# Medicop_Schematic.net
KiCad netlist of a schematic drawn in Altium Designer
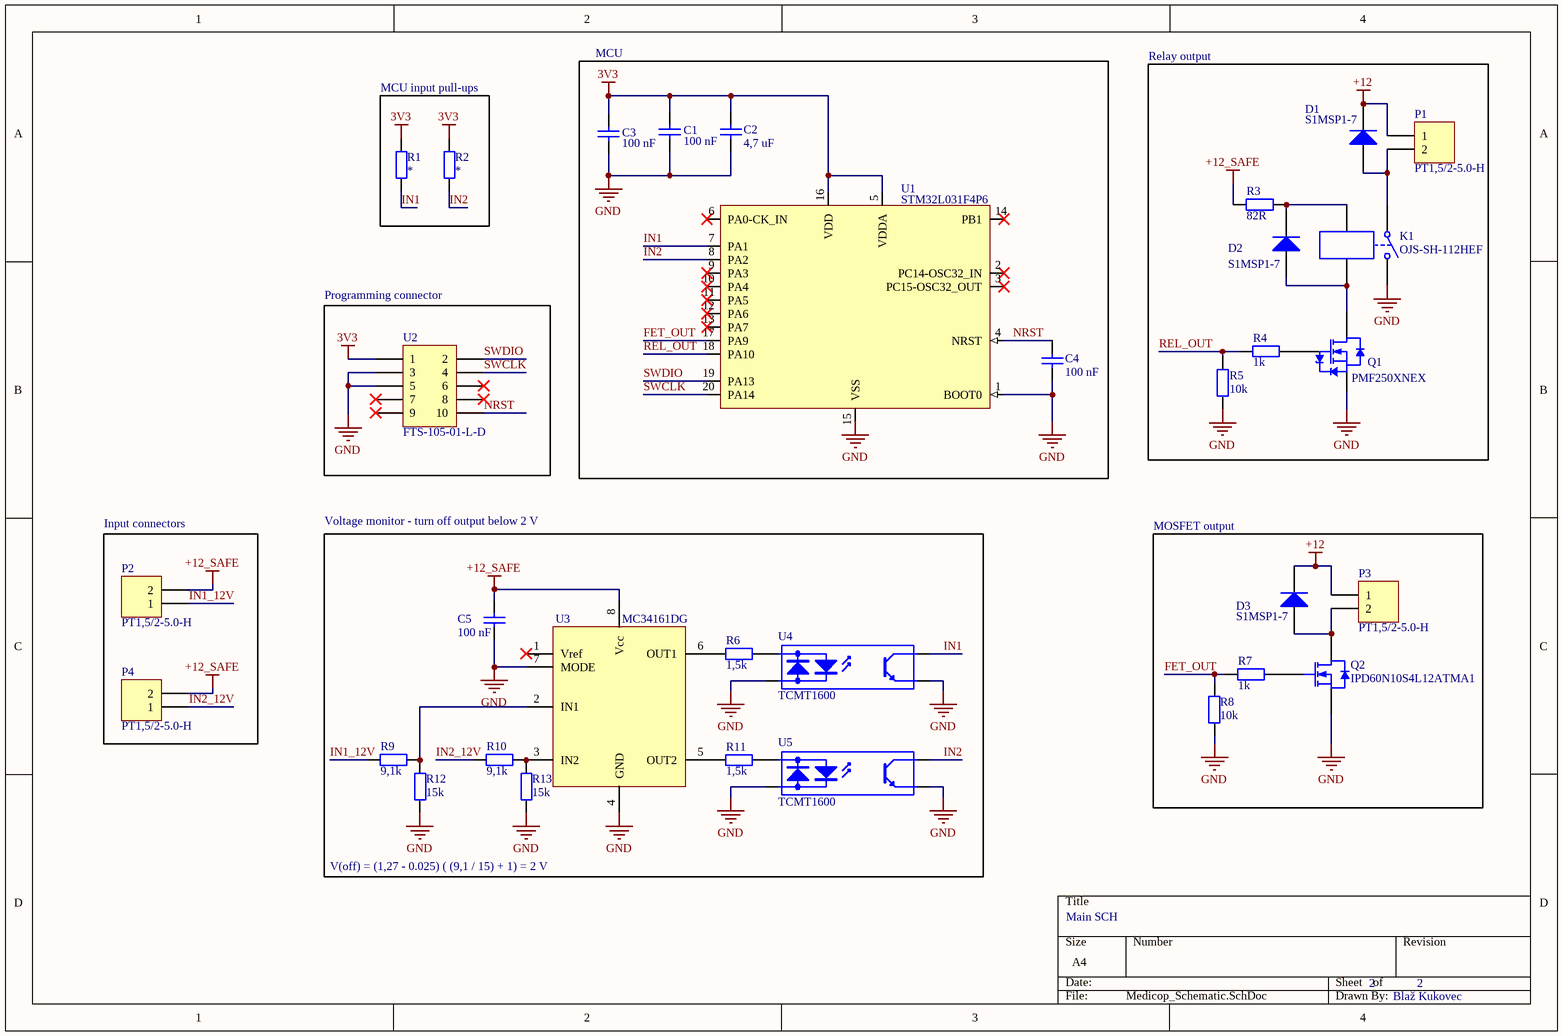
[diagram p0: Medicop_Schematic.SchDoc]

(export (version "E")
  (design (tool "Eeschema 10.0.6"))
  (components
    (comp (ref "C1")
      (value "100 nF")
      (footprint "C0603[1608]")
      (description "Capacitor")
      (fields (field (name "Comment") "Cap"))
      (libsource (lib "BK_Library") (part "Cap"))
    )
    (comp (ref "C2")
      (value "4,7 uF")
      (footprint "C0603[1608]")
      (description "Capacitor")
      (fields (field (name "Comment") "Cap"))
      (libsource (lib "BK_Library") (part "Cap"))
    )
    (comp (ref "C3")
      (value "100 nF")
      (footprint "C0603[1608]")
      (description "Capacitor")
      (fields (field (name "Comment") "Cap"))
      (libsource (lib "BK_Library") (part "Cap"))
    )
    (comp (ref "C4")
      (value "100 nF")
      (footprint "C0603[1608]")
      (description "Capacitor")
      (fields (field (name "Comment") "Cap"))
      (libsource (lib "BK_Library") (part "Cap"))
    )
    (comp (ref "C5")
      (value "100 nF")
      (footprint "C0603[1608]")
      (description "Capacitor")
      (fields (field (name "Comment") "Cap"))
      (libsource (lib "BK_Library") (part "Cap"))
    )
    (comp (ref "D1")
      (value "S1MSP1-7")
      (footprint "PowerDI123")
      (description "S1MSP1-7 -  Standard Power Diode")
      (libsource (lib "BK_Library") (part "S1MSP1-7"))
    )
    (comp (ref "D2")
      (value "S1MSP1-7")
      (footprint "PowerDI123")
      (description "S1MSP1-7 -  Standard Power Diode")
      (libsource (lib "BK_Library") (part "S1MSP1-7"))
    )
    (comp (ref "D3")
      (value "S1MSP1-7")
      (footprint "PowerDI123")
      (description "S1MSP1-7 -  Standard Power Diode")
      (libsource (lib "BK_Library") (part "S1MSP1-7"))
    )
    (comp (ref "K1")
      (value "OJS-SH-112HEF")
      (description "Power Relay, SPST-NO, 12 VDC, 16 A, OJS, Through Hole, Non Latching")
      (libsource (lib "BK_Library") (part "OJS-SH-112HEF"))
    )
    (comp (ref "P1")
      (value "PT1,5/2-5.0-H")
      (footprint "PT1,5/2-5.0-H")
      (description "Wire-To-Board Terminal Block, 5 mm, 2 Ways, 1.5 mm²")
      (libsource (lib "") (part "PT1,5/2-5.0-H_1"))
    )
    (comp (ref "P2")
      (value "PT1,5/2-5.0-H")
      (footprint "PT1,5/2-5.0-H")
      (description "Wire-To-Board Terminal Block, 5 mm, 2 Ways, 1.5 mm²")
      (libsource (lib "BK_Library") (part "PT1,5/2-5.0-H"))
    )
    (comp (ref "P3")
      (value "PT1,5/2-5.0-H")
      (footprint "PT1,5/2-5.0-H")
      (description "Wire-To-Board Terminal Block, 5 mm, 2 Ways, 1.5 mm²")
      (libsource (lib "") (part "PT1,5/2-5.0-H_1"))
    )
    (comp (ref "P4")
      (value "PT1,5/2-5.0-H")
      (footprint "PT1,5/2-5.0-H")
      (description "Wire-To-Board Terminal Block, 5 mm, 2 Ways, 1.5 mm²")
      (libsource (lib "BK_Library") (part "PT1,5/2-5.0-H"))
    )
    (comp (ref "Q1")
      (value "PMF250XNEX")
      (footprint "SC-70 (SOT323)")
      (description "Power MOSFET, N Channel, 30 V, 900 mA, 0.212 ohm")
      (libsource (lib "BK_Library") (part "PMF250XNEX"))
    )
    (comp (ref "Q2")
      (value "IPD60N10S4L12ATMA1")
      (footprint "DPAK (TO-252)")
      (description "Power MOSFET, N Channel, 100 V, 60 A, 0.0098 ohm, TO-252 (DPAK), Surface Mount")
      (libsource (lib "BK_Library") (part "IPD60N10S4L12ATMA1"))
    )
    (comp (ref "R1")
      (value "Res")
      (footprint "R0603[1608]")
      (description "Resistor")
      (fields (field (name "ALTIUM_VALUE") "*"))
      (libsource (lib "") (part "Res_1"))
    )
    (comp (ref "R2")
      (value "Res")
      (footprint "R0603[1608]")
      (description "Resistor")
      (fields (field (name "ALTIUM_VALUE") "*"))
      (libsource (lib "") (part "Res_1"))
    )
    (comp (ref "R3")
      (value "82R")
      (footprint "R1206[3216]")
      (description "Resistor")
      (fields (field (name "Comment") "Res"))
      (libsource (lib "") (part "Res_3"))
    )
    (comp (ref "R4")
      (value "1k")
      (footprint "R0603[1608]")
      (description "Resistor")
      (fields (field (name "Comment") "Res"))
      (libsource (lib "") (part "Res_3"))
    )
    (comp (ref "R5")
      (value "10k")
      (footprint "R0603[1608]")
      (description "Resistor")
      (fields (field (name "Comment") "Res"))
      (libsource (lib "") (part "Res_1"))
    )
    (comp (ref "R6")
      (value "1,5k")
      (footprint "R1206[3216]")
      (description "Resistor")
      (fields (field (name "Comment") "Res"))
      (libsource (lib "BK_Library") (part "Res"))
    )
    (comp (ref "R7")
      (value "1k")
      (footprint "R0603[1608]")
      (description "Resistor")
      (fields (field (name "Comment") "Res"))
      (libsource (lib "BK_Library") (part "Res"))
    )
    (comp (ref "R8")
      (value "10k")
      (footprint "R0603[1608]")
      (description "Resistor")
      (fields (field (name "Comment") "Res"))
      (libsource (lib "") (part "Res_2"))
    )
    (comp (ref "R9")
      (value "9,1k")
      (footprint "R0603[1608]")
      (description "Resistor")
      (fields (field (name "Comment") "Res"))
      (libsource (lib "") (part "Res_3"))
    )
    (comp (ref "R10")
      (value "9,1k")
      (footprint "R0603[1608]")
      (description "Resistor")
      (fields (field (name "Comment") "Res"))
      (libsource (lib "") (part "Res_3"))
    )
    (comp (ref "R11")
      (value "1,5k")
      (footprint "R1206[3216]")
      (description "Resistor")
      (fields (field (name "Comment") "Res"))
      (libsource (lib "BK_Library") (part "Res"))
    )
    (comp (ref "R12")
      (value "15k")
      (footprint "R0603[1608]")
      (description "Resistor")
      (fields (field (name "Comment") "Res"))
      (libsource (lib "") (part "Res_1"))
    )
    (comp (ref "R13")
      (value "15k")
      (footprint "R0603[1608]")
      (description "Resistor")
      (fields (field (name "Comment") "Res"))
      (libsource (lib "") (part "Res_1"))
    )
    (comp (ref "U1")
      (value "STM32L031F4P6")
      (footprint "TSSOP-20")
      (libsource (lib "BK_Library") (part "STM32L031F4P6"))
    )
    (comp (ref "U2")
      (value "FTS-105-01-L-D")
      (footprint "CON10_2x5_TU_FTS_SAI")
      (description "Pin Header, Wire-to-Board, 1.27 mm, 2 Rows, 10 Contacts, Through Hole, FTS")
      (libsource (lib "BK_Library") (part "FTS-105-01-L-D"))
    )
    (comp (ref "U3")
      (value "MC34161DG")
      (footprint "SOIC-8")
      (description "Voltage Monitor, 2 Monitors, 2 V to 40 V Supply, 1.27 V Threshold, Active-Low, MSOP-8")
      (libsource (lib "BK_Library") (part "MC34161DG"))
    )
    (comp (ref "U4") (value "TCMT1600") (footprint "SOP-4") (libsource (lib "BK_Library") (part "TCMT1600")))
    (comp (ref "U5") (value "TCMT1600") (footprint "SOP-4") (libsource (lib "BK_Library") (part "TCMT1600")))
  )
  (nets
    (net (code "1") (name "+12") (class "Default")
      (node (ref "D1") (pin "2") (pinfunction "K_2") (pintype "passive"))
      (node (ref "D3") (pin "2") (pinfunction "K_2") (pintype "passive"))
      (node (ref "P1") (pin "1") (pinfunction "1_1") (pintype "passive"))
      (node (ref "P3") (pin "1") (pinfunction "1_1") (pintype "passive"))
    )
    (net (code "2") (name "+12_SAFE") (class "Default")
      (node (ref "C5") (pin "2") (pinfunction "2_2") (pintype "passive"))
      (node (ref "P2") (pin "2") (pinfunction "2_2") (pintype "passive"))
      (node (ref "P4") (pin "2") (pinfunction "2_2") (pintype "passive"))
      (node (ref "R3") (pin "2") (pinfunction "2_2") (pintype "passive"))
      (node (ref "U3") (pin "8") (pinfunction "Vcc_8") (pintype "passive"))
    )
    (net (code "3") (name "/FET_OUT") (class "Default")
      (node (ref "R7") (pin "1") (pinfunction "1_1") (pintype "passive"))
      (node (ref "R8") (pin "1") (pinfunction "1_1") (pintype "passive"))
      (node (ref "U1") (pin "17") (pinfunction "PA9_17") (pintype "passive"))
    )
    (net (code "4") (name "/IN1") (class "Default")
      (node (ref "R1") (pin "1") (pinfunction "1_1") (pintype "passive"))
      (node (ref "U1") (pin "7") (pinfunction "PA1_7") (pintype "passive"))
      (node (ref "U4") (pin "4") (pinfunction "C_4") (pintype "passive"))
    )
    (net (code "5") (name "/IN1_12V") (class "Default")
      (node (ref "P2") (pin "1") (pinfunction "1_1") (pintype "passive"))
      (node (ref "R9") (pin "2") (pinfunction "2_2") (pintype "passive"))
    )
    (net (code "6") (name "/IN2") (class "Default")
      (node (ref "R2") (pin "1") (pinfunction "1_1") (pintype "passive"))
      (node (ref "U1") (pin "8") (pinfunction "PA2_8") (pintype "passive"))
      (node (ref "U5") (pin "4") (pinfunction "C_4") (pintype "passive"))
    )
    (net (code "7") (name "/IN2_12V") (class "Default")
      (node (ref "P4") (pin "1") (pinfunction "1_1") (pintype "passive"))
      (node (ref "R10") (pin "2") (pinfunction "2_2") (pintype "passive"))
    )
    (net (code "8") (name "/NRST") (class "Default")
      (node (ref "C4") (pin "2") (pinfunction "2_2") (pintype "passive"))
      (node (ref "U1") (pin "4") (pinfunction "NRST_4") (pintype "input"))
      (node (ref "U2") (pin "10") (pinfunction "10_10") (pintype "passive"))
    )
    (net (code "9") (name "/REL_OUT") (class "Default")
      (node (ref "R4") (pin "2") (pinfunction "2_2") (pintype "passive"))
      (node (ref "R5") (pin "2") (pinfunction "2_2") (pintype "passive"))
      (node (ref "U1") (pin "18") (pinfunction "PA10_18") (pintype "passive"))
    )
    (net (code "10") (name "/SWCLK") (class "Default")
      (node (ref "U1") (pin "20") (pinfunction "PA14_20") (pintype "passive"))
      (node (ref "U2") (pin "4") (pinfunction "4_4") (pintype "passive"))
    )
    (net (code "11") (name "/SWDIO") (class "Default")
      (node (ref "U1") (pin "19") (pinfunction "PA13_19") (pintype "passive"))
      (node (ref "U2") (pin "2") (pinfunction "2_2") (pintype "passive"))
    )
    (net (code "12") (name "3V3") (class "Default")
      (node (ref "C1") (pin "2") (pinfunction "2_2") (pintype "passive"))
      (node (ref "C2") (pin "2") (pinfunction "2_2") (pintype "passive"))
      (node (ref "C3") (pin "2") (pinfunction "2_2") (pintype "passive"))
      (node (ref "R1") (pin "2") (pinfunction "2_2") (pintype "passive"))
      (node (ref "R2") (pin "2") (pinfunction "2_2") (pintype "passive"))
      (node (ref "U1") (pin "16") (pinfunction "VDD_16") (pintype "power_in"))
      (node (ref "U1") (pin "5") (pinfunction "VDDA_5") (pintype "power_in"))
      (node (ref "U2") (pin "1") (pinfunction "1_1") (pintype "passive"))
    )
    (net (code "13") (name "GND") (class "Default")
      (node (ref "C1") (pin "1") (pinfunction "1_1") (pintype "passive"))
      (node (ref "C2") (pin "1") (pinfunction "1_1") (pintype "passive"))
      (node (ref "C3") (pin "1") (pinfunction "1_1") (pintype "passive"))
      (node (ref "C4") (pin "1") (pinfunction "1_1") (pintype "passive"))
      (node (ref "C5") (pin "1") (pinfunction "1_1") (pintype "passive"))
      (node (ref "K1") (pin "2") (pinfunction "2_2") (pintype "passive"))
      (node (ref "Q1") (pin "2") (pinfunction "S_2") (pintype "passive"))
      (node (ref "Q2") (pin "3") (pinfunction "S_3") (pintype "passive"))
      (node (ref "R12") (pin "1") (pinfunction "1_1") (pintype "passive"))
      (node (ref "R13") (pin "1") (pinfunction "1_1") (pintype "passive"))
      (node (ref "R5") (pin "1") (pinfunction "1_1") (pintype "passive"))
      (node (ref "R8") (pin "2") (pinfunction "2_2") (pintype "passive"))
      (node (ref "U1") (pin "1") (pinfunction "BOOT0_1") (pintype "input"))
      (node (ref "U1") (pin "15") (pinfunction "VSS_15") (pintype "power_in"))
      (node (ref "U2") (pin "3") (pinfunction "3_3") (pintype "passive"))
      (node (ref "U2") (pin "5") (pinfunction "5_5") (pintype "passive"))
      (node (ref "U3") (pin "4") (pinfunction "GND_4") (pintype "passive"))
      (node (ref "U3") (pin "7") (pinfunction "MODE_7") (pintype "passive"))
      (node (ref "U4") (pin "2") (pinfunction "K_2") (pintype "passive"))
      (node (ref "U4") (pin "3") (pinfunction "E_3") (pintype "passive"))
      (node (ref "U5") (pin "2") (pinfunction "K_2") (pintype "passive"))
      (node (ref "U5") (pin "3") (pinfunction "E_3") (pintype "passive"))
    )
    (net (code "14") (name "Net-(D1-A)") (class "Default")
      (node (ref "D1") (pin "1") (pinfunction "A_1") (pintype "passive"))
      (node (ref "K1") (pin "1") (pinfunction "1_1") (pintype "passive"))
      (node (ref "P1") (pin "2") (pinfunction "2_2") (pintype "passive"))
    )
    (net (code "15") (name "Net-(D2-A)") (class "Default")
      (node (ref "D2") (pin "1") (pinfunction "A_1") (pintype "passive"))
      (node (ref "K1") (pin "4") (pinfunction "4_4") (pintype "passive"))
      (node (ref "Q1") (pin "3") (pinfunction "D_3") (pintype "passive"))
    )
    (net (code "16") (name "Net-(D2-K)") (class "Default")
      (node (ref "D2") (pin "2") (pinfunction "K_2") (pintype "passive"))
      (node (ref "K1") (pin "3") (pinfunction "3_3") (pintype "passive"))
      (node (ref "R3") (pin "1") (pinfunction "1_1") (pintype "passive"))
    )
    (net (code "17") (name "Net-(D3-A)") (class "Default")
      (node (ref "D3") (pin "1") (pinfunction "A_1") (pintype "passive"))
      (node (ref "P3") (pin "2") (pinfunction "2_2") (pintype "passive"))
      (node (ref "Q2") (pin "2") (pinfunction "D_2") (pintype "passive"))
    )
    (net (code "18") (name "Net-(Q1-G)") (class "Default")
      (node (ref "Q1") (pin "1") (pinfunction "G_1") (pintype "passive"))
      (node (ref "R4") (pin "1") (pinfunction "1_1") (pintype "passive"))
    )
    (net (code "19") (name "Net-(Q2-G)") (class "Default")
      (node (ref "Q2") (pin "1") (pinfunction "G_1") (pintype "passive"))
      (node (ref "R7") (pin "2") (pinfunction "2_2") (pintype "passive"))
    )
    (net (code "20") (name "Net-(U3-IN1)") (class "Default")
      (node (ref "R12") (pin "2") (pinfunction "2_2") (pintype "passive"))
      (node (ref "R9") (pin "1") (pinfunction "1_1") (pintype "passive"))
      (node (ref "U3") (pin "2") (pinfunction "IN1_2") (pintype "passive"))
    )
    (net (code "21") (name "Net-(U3-IN2)") (class "Default")
      (node (ref "R10") (pin "1") (pinfunction "1_1") (pintype "passive"))
      (node (ref "R13") (pin "2") (pinfunction "2_2") (pintype "passive"))
      (node (ref "U3") (pin "3") (pinfunction "IN2_3") (pintype "passive"))
    )
    (net (code "22") (name "Net-(U3-OUT1)") (class "Default")
      (node (ref "R6") (pin "1") (pinfunction "1_1") (pintype "passive"))
      (node (ref "U3") (pin "6") (pinfunction "OUT1_6") (pintype "passive"))
    )
    (net (code "23") (name "Net-(U3-OUT2)") (class "Default")
      (node (ref "R11") (pin "1") (pinfunction "1_1") (pintype "passive"))
      (node (ref "U3") (pin "5") (pinfunction "OUT2_5") (pintype "passive"))
    )
    (net (code "24") (name "Net-(U4-A)") (class "Default")
      (node (ref "R6") (pin "2") (pinfunction "2_2") (pintype "passive"))
      (node (ref "U4") (pin "1") (pinfunction "A_1") (pintype "passive"))
    )
    (net (code "25") (name "Net-(U5-A)") (class "Default")
      (node (ref "R11") (pin "2") (pinfunction "2_2") (pintype "passive"))
      (node (ref "U5") (pin "1") (pinfunction "A_1") (pintype "passive"))
    )
    (net (code "26") (name "unconnected-(U1-PA0-CK_IN-Pad6)") (class "Default")
      (node (ref "U1") (pin "6") (pinfunction "PA0-CK_IN_6") (pintype "passive+no_connect"))
    )
    (net (code "27") (name "unconnected-(U1-PA3-Pad9)") (class "Default")
      (node (ref "U1") (pin "9") (pinfunction "PA3_9") (pintype "passive+no_connect"))
    )
    (net (code "28") (name "unconnected-(U1-PA4-Pad10)") (class "Default")
      (node (ref "U1") (pin "10") (pinfunction "PA4_10") (pintype "passive+no_connect"))
    )
    (net (code "29") (name "unconnected-(U1-PA5-Pad11)") (class "Default")
      (node (ref "U1") (pin "11") (pinfunction "PA5_11") (pintype "passive+no_connect"))
    )
    (net (code "30") (name "unconnected-(U1-PA6-Pad12)") (class "Default")
      (node (ref "U1") (pin "12") (pinfunction "PA6_12") (pintype "passive+no_connect"))
    )
    (net (code "31") (name "unconnected-(U1-PA7-Pad13)") (class "Default")
      (node (ref "U1") (pin "13") (pinfunction "PA7_13") (pintype "passive+no_connect"))
    )
    (net (code "32") (name "unconnected-(U1-PB1-Pad14)") (class "Default")
      (node (ref "U1") (pin "14") (pinfunction "PB1_14") (pintype "passive+no_connect"))
    )
    (net (code "33") (name "unconnected-(U1-PC14-OSC32_IN-Pad2)") (class "Default")
      (node (ref "U1") (pin "2") (pinfunction "PC14-OSC32_IN_2") (pintype "passive+no_connect"))
    )
    (net (code "34") (name "unconnected-(U1-PC15-OSC32_OUT-Pad3)") (class "Default")
      (node (ref "U1") (pin "3") (pinfunction "PC15-OSC32_OUT_3") (pintype "passive+no_connect"))
    )
    (net (code "35") (name "unconnected-(U2-Pad6)") (class "Default")
      (node (ref "U2") (pin "6") (pinfunction "6_6") (pintype "passive+no_connect"))
    )
    (net (code "36") (name "unconnected-(U2-Pad7)") (class "Default")
      (node (ref "U2") (pin "7") (pinfunction "7_7") (pintype "passive+no_connect"))
    )
    (net (code "37") (name "unconnected-(U2-Pad8)") (class "Default")
      (node (ref "U2") (pin "8") (pinfunction "8_8") (pintype "passive+no_connect"))
    )
    (net (code "38") (name "unconnected-(U2-Pad9)") (class "Default")
      (node (ref "U2") (pin "9") (pinfunction "9_9") (pintype "passive+no_connect"))
    )
    (net (code "39") (name "unconnected-(U3-Vref-Pad1)") (class "Default")
      (node (ref "U3") (pin "1") (pinfunction "Vref_1") (pintype "passive+no_connect"))
    )
  )
)
